# TEMP_CTRL.net
KiCad netlist of a schematic drawn in Altium Designer
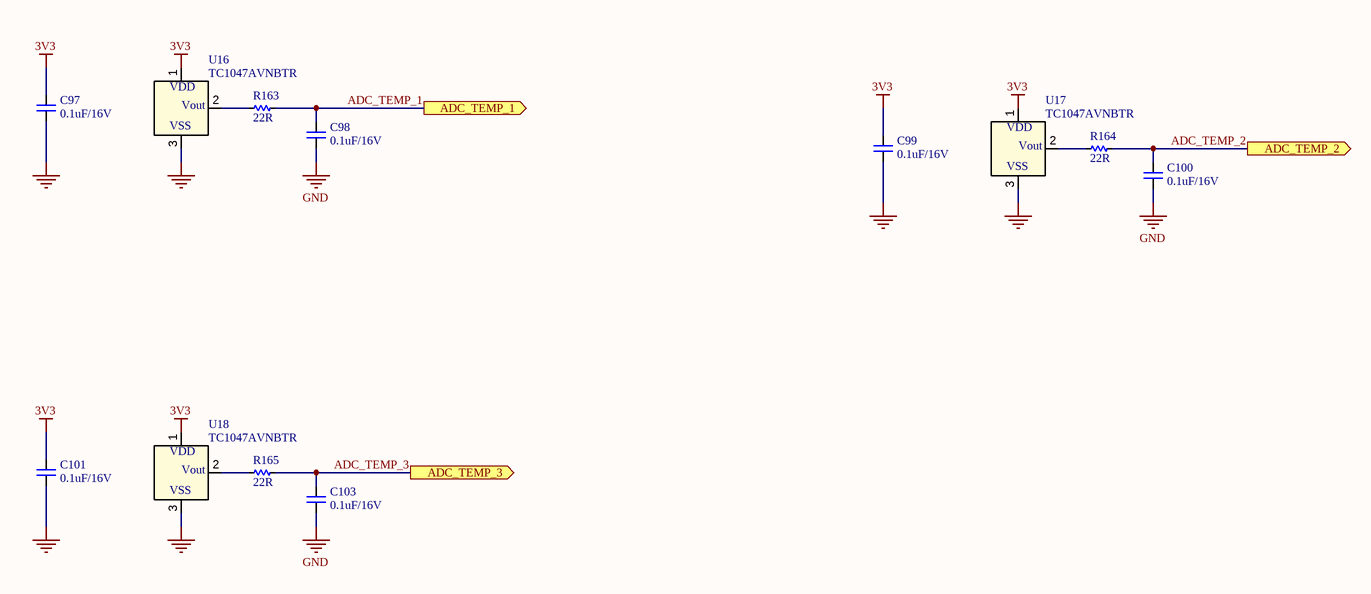
[diagram p0: TEMP_CTRL.SchDoc]

(export (version "E")
  (design (tool "Eeschema 10.0.6"))
  (components
    (comp (ref "C97")
      (value "0.1uF/16V")
      (footprint "CAP_C_1608X80")
      (description "CAP_Chip")
      (libsource (lib "LABLIB") (part "CAP_SMD"))
    )
    (comp (ref "C98")
      (value "0.1uF/16V")
      (footprint "CAP_C_1608X80")
      (description "CAP_Chip")
      (libsource (lib "LABLIB") (part "CAP_SMD"))
    )
    (comp (ref "C99")
      (value "0.1uF/16V")
      (footprint "CAP_C_1608X80")
      (description "CAP_Chip")
      (libsource (lib "LABLIB") (part "CAP_SMD"))
    )
    (comp (ref "C100")
      (value "0.1uF/16V")
      (footprint "CAP_C_1608X80")
      (description "CAP_Chip")
      (libsource (lib "LABLIB") (part "CAP_SMD"))
    )
    (comp (ref "C101")
      (value "0.1uF/16V")
      (footprint "CAP_C_1608X80")
      (description "CAP_Chip")
      (libsource (lib "LABLIB") (part "CAP_SMD"))
    )
    (comp (ref "C103")
      (value "0.1uF/16V")
      (footprint "CAP_C_1608X80")
      (description "CAP_Chip")
      (libsource (lib "LABLIB") (part "CAP_SMD"))
    )
    (comp (ref "R163")
      (value "22R")
      (footprint "RES_C_1608X60")
      (description "RES")
      (libsource (lib "LABLIB") (part "_RES_B_2"))
    )
    (comp (ref "R164")
      (value "22R")
      (footprint "RES_C_1608X60")
      (description "RES")
      (libsource (lib "LABLIB") (part "_RES_B_2"))
    )
    (comp (ref "R165")
      (value "22R")
      (footprint "RES_C_1608X60")
      (description "RES")
      (libsource (lib "LABLIB") (part "_RES_B_2"))
    )
    (comp (ref "U16")
      (value "TC1047AVNBTR")
      (footprint "SOT-23_MC_MCH")
      (description "No Description Available")
      (fields (field (name "COPYRIGHT") "Copyright (C) 2025 Ultra Librarian. All rights reserved."))
      (libsource (lib "COMM_SCHLIB") (part "TC1047AVNBTR"))
    )
    (comp (ref "U17")
      (value "TC1047AVNBTR")
      (footprint "SOT-23_MC_MCH")
      (description "No Description Available")
      (fields (field (name "COPYRIGHT") "Copyright (C) 2025 Ultra Librarian. All rights reserved."))
      (libsource (lib "COMM_SCHLIB") (part "TC1047AVNBTR"))
    )
    (comp (ref "U18")
      (value "TC1047AVNBTR")
      (footprint "SOT-23_MC_MCH")
      (description "No Description Available")
      (fields (field (name "COPYRIGHT") "Copyright (C) 2025 Ultra Librarian. All rights reserved."))
      (libsource (lib "COMM_SCHLIB") (part "TC1047AVNBTR"))
    )
  )
  (nets
    (net (code "1") (name "/ADC_TEMP_1") (class "Default")
      (node (ref "C98") (pin "2") (pinfunction "2_2") (pintype "passive"))
      (node (ref "R163") (pin "2") (pinfunction "2_2") (pintype "passive"))
    )
    (net (code "2") (name "/ADC_TEMP_2") (class "Default")
      (node (ref "C100") (pin "2") (pinfunction "2_2") (pintype "passive"))
      (node (ref "R164") (pin "2") (pinfunction "2_2") (pintype "passive"))
    )
    (net (code "3") (name "/ADC_TEMP_3") (class "Default")
      (node (ref "C103") (pin "2") (pinfunction "2_2") (pintype "passive"))
      (node (ref "R165") (pin "2") (pinfunction "2_2") (pintype "passive"))
    )
    (net (code "4") (name "3V3") (class "Default")
      (node (ref "C101") (pin "2") (pinfunction "2_2") (pintype "passive"))
      (node (ref "C97") (pin "2") (pinfunction "2_2") (pintype "passive"))
      (node (ref "C99") (pin "2") (pinfunction "2_2") (pintype "passive"))
      (node (ref "U16") (pin "1") (pinfunction "VDD_1") (pintype "passive"))
      (node (ref "U17") (pin "1") (pinfunction "VDD_1") (pintype "passive"))
      (node (ref "U18") (pin "1") (pinfunction "VDD_1") (pintype "passive"))
    )
    (net (code "5") (name "GND") (class "Default")
      (node (ref "C100") (pin "1") (pinfunction "1_1") (pintype "passive"))
      (node (ref "C101") (pin "1") (pinfunction "1_1") (pintype "passive"))
      (node (ref "C103") (pin "1") (pinfunction "1_1") (pintype "passive"))
      (node (ref "C97") (pin "1") (pinfunction "1_1") (pintype "passive"))
      (node (ref "C98") (pin "1") (pinfunction "1_1") (pintype "passive"))
      (node (ref "C99") (pin "1") (pinfunction "1_1") (pintype "passive"))
      (node (ref "U16") (pin "3") (pinfunction "VSS_3") (pintype "passive"))
      (node (ref "U17") (pin "3") (pinfunction "VSS_3") (pintype "passive"))
      (node (ref "U18") (pin "3") (pinfunction "VSS_3") (pintype "passive"))
    )
    (net (code "6") (name "Net-(U16-VOUT)") (class "Default")
      (node (ref "R163") (pin "1") (pinfunction "1_1") (pintype "passive"))
      (node (ref "U16") (pin "2") (pinfunction "VOUT_2") (pintype "passive"))
    )
    (net (code "7") (name "Net-(U17-VOUT)") (class "Default")
      (node (ref "R164") (pin "1") (pinfunction "1_1") (pintype "passive"))
      (node (ref "U17") (pin "2") (pinfunction "VOUT_2") (pintype "passive"))
    )
    (net (code "8") (name "Net-(U18-VOUT)") (class "Default")
      (node (ref "R165") (pin "1") (pinfunction "1_1") (pintype "passive"))
      (node (ref "U18") (pin "2") (pinfunction "VOUT_2") (pintype "passive"))
    )
  )
)
